# REP_-_Rev3.net
KiCad netlist of a schematic drawn in EAGLE
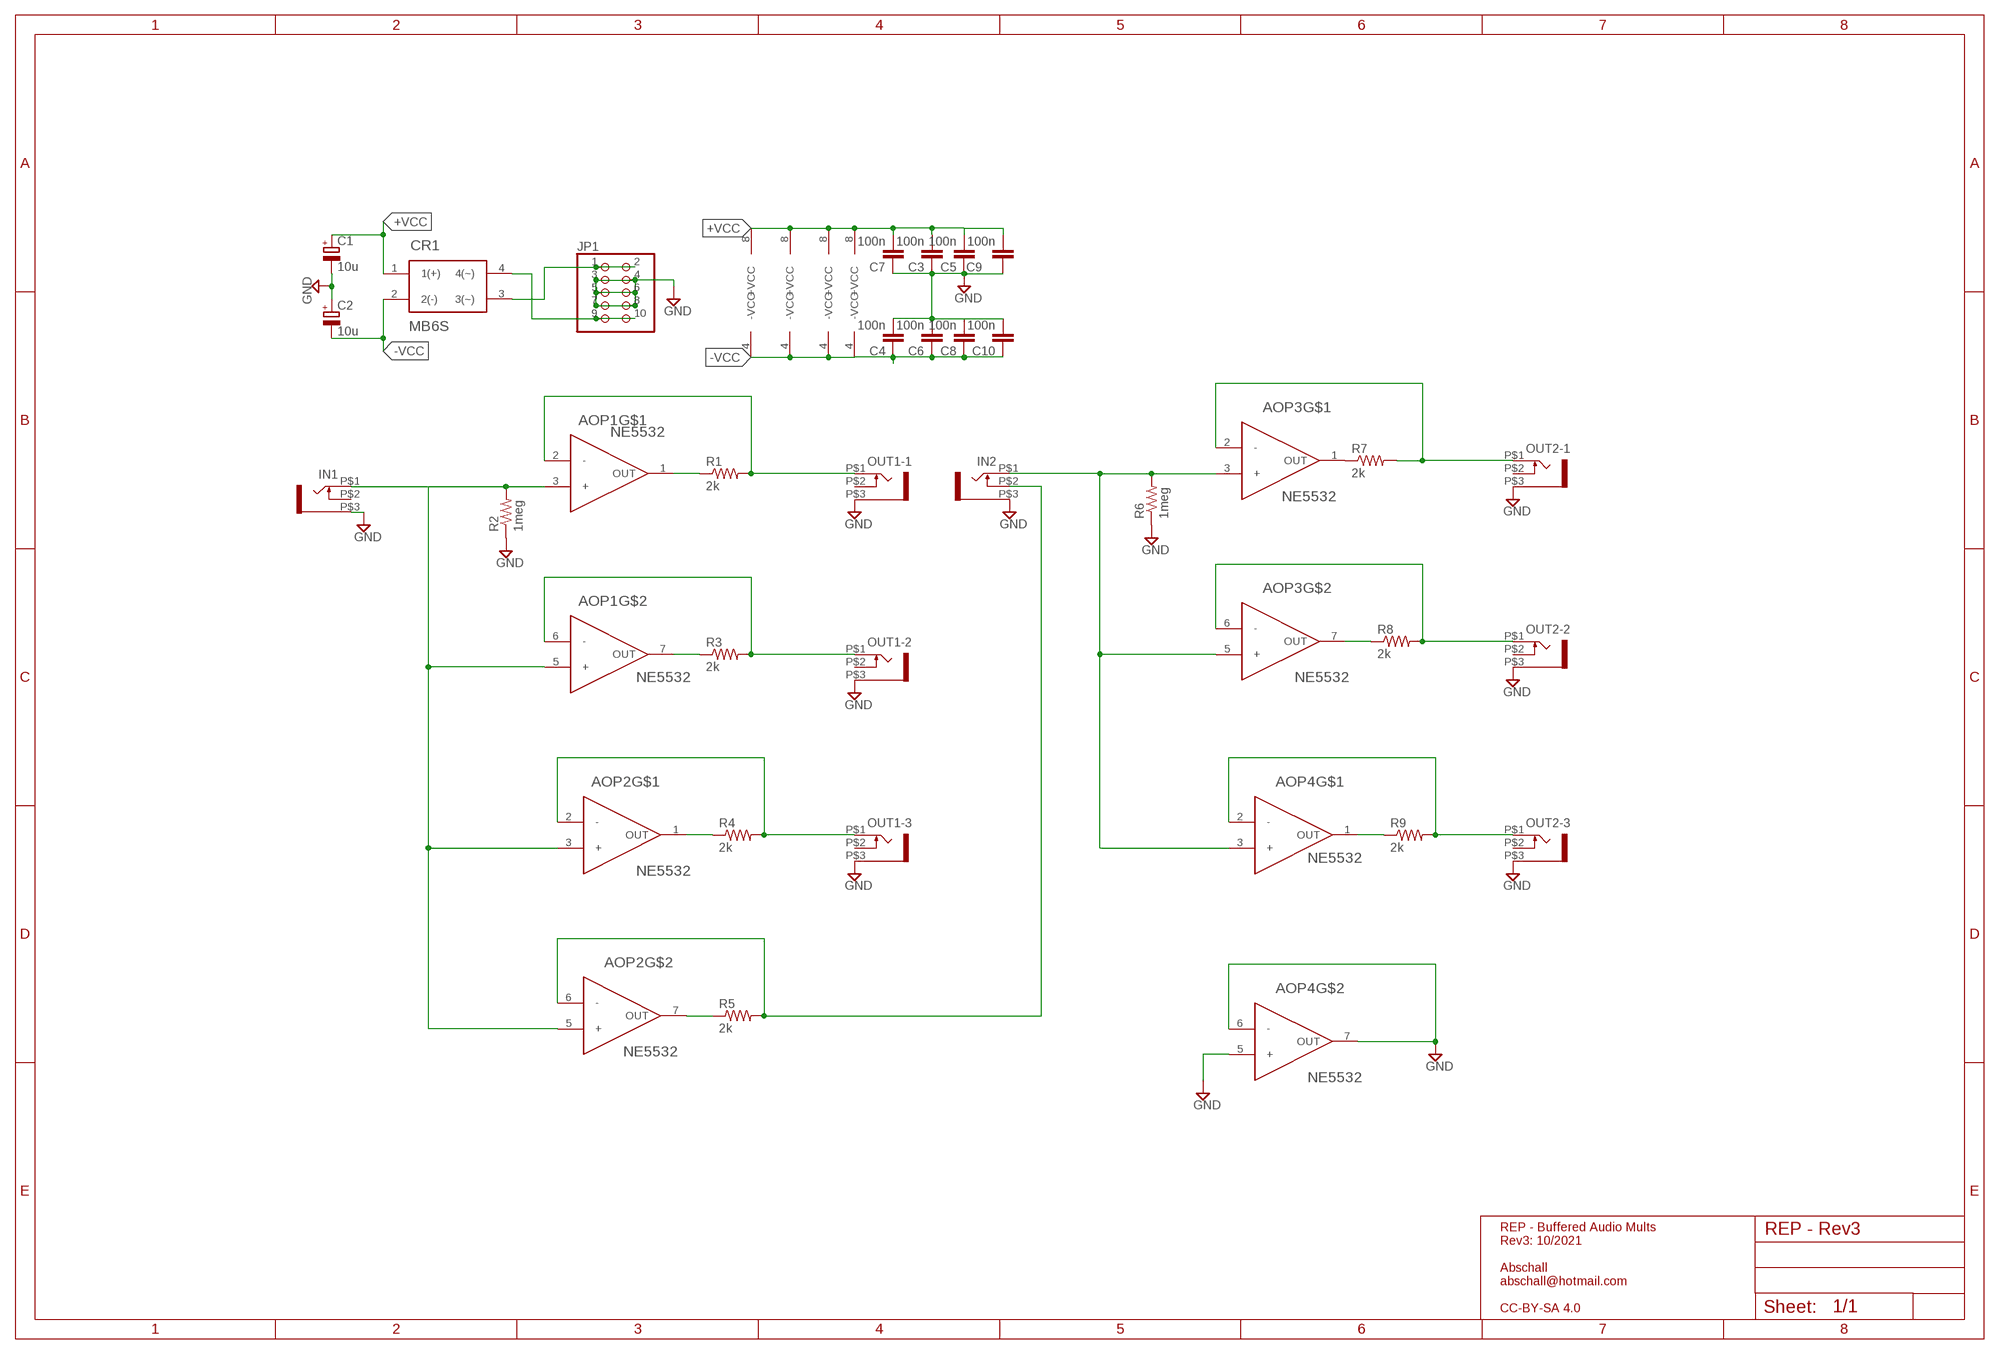
[diagram p0: schematic, sheet 1]

(export (version "E")
  (design (tool "Eeschema 10.0.6"))
  (components
    (comp (ref "AOP1")
      (value "NE5532")
      (footprint "eagle-import:SOIC8")
      (libsource (lib "eagle-import") (part "TL072ACDR"))
    )
    (comp (ref "AOP2")
      (value "NE5532")
      (footprint "eagle-import:SOIC8")
      (libsource (lib "eagle-import") (part "TL072ACDR"))
    )
    (comp (ref "AOP3")
      (value "NE5532")
      (footprint "eagle-import:SOIC8")
      (libsource (lib "eagle-import") (part "TL072ACDR"))
    )
    (comp (ref "AOP4")
      (value "NE5532")
      (footprint "eagle-import:SOIC8")
      (libsource (lib "eagle-import") (part "TL072ACDR"))
    )
    (comp (ref "C1")
      (value "10u")
      (footprint "eagle-import:PANASONIC_B")
      (libsource (lib "eagle-import") (part "CPOL-EUB"))
    )
    (comp (ref "C2")
      (value "10u")
      (footprint "eagle-import:PANASONIC_B")
      (libsource (lib "eagle-import") (part "CPOL-EUB"))
    )
    (comp (ref "C3")
      (value "100n")
      (footprint "eagle-import:C0805")
      (libsource (lib "eagle-import") (part "C-EUC0805"))
    )
    (comp (ref "C4")
      (value "100n")
      (footprint "eagle-import:C0805")
      (libsource (lib "eagle-import") (part "C-EUC0805"))
    )
    (comp (ref "C5")
      (value "100n")
      (footprint "eagle-import:C0805")
      (libsource (lib "eagle-import") (part "C-EUC0805"))
    )
    (comp (ref "C6")
      (value "100n")
      (footprint "eagle-import:C0805")
      (libsource (lib "eagle-import") (part "C-EUC0805"))
    )
    (comp (ref "C7")
      (value "100n")
      (footprint "eagle-import:C0805")
      (libsource (lib "eagle-import") (part "C-EUC0805"))
    )
    (comp (ref "C8")
      (value "100n")
      (footprint "eagle-import:C0805")
      (libsource (lib "eagle-import") (part "C-EUC0805"))
    )
    (comp (ref "C9")
      (value "100n")
      (footprint "eagle-import:C0805")
      (libsource (lib "eagle-import") (part "C-EUC0805"))
    )
    (comp (ref "C10")
      (value "100n")
      (footprint "eagle-import:C0805")
      (libsource (lib "eagle-import") (part "C-EUC0805"))
    )
    (comp (ref "CR1")
      (value "MB6S")
      (footprint "eagle-import:4SOIC")
      (fields
        (field (name "DIGIKEY_PARTNO") "MB6SCT-ND")
        (field (name "MANUFACTURER") "ON Semiconductor")
        (field (name "CREATED_BY") "PCBLayout.com")
      )
      (libsource (lib "eagle-import") (part "MB6S"))
    )
    (comp (ref "IN1")
      (value "WQP-PJ301M-12_JACK")
      (footprint "eagle-import:WQP-PJ301M-12_JACK")
      (libsource (lib "eagle-import") (part "WQP-PJ301M-12_JACK"))
    )
    (comp (ref "IN2")
      (value "WQP-PJ301M-12_JACK")
      (footprint "eagle-import:WQP-PJ301M-12_JACK")
      (libsource (lib "eagle-import") (part "WQP-PJ301M-12_JACK"))
    )
    (comp (ref "JP1")
      (value "PINHD-2X5")
      (footprint "eagle-import:2X05")
      (libsource (lib "eagle-import") (part "PINHD-2X5"))
    )
    (comp (ref "OUT1-1")
      (value "WQP-PJ301M-12_JACK")
      (footprint "eagle-import:WQP-PJ301M-12_JACK")
      (libsource (lib "eagle-import") (part "WQP-PJ301M-12_JACK"))
    )
    (comp (ref "OUT1-2")
      (value "WQP-PJ301M-12_JACK")
      (footprint "eagle-import:WQP-PJ301M-12_JACK")
      (libsource (lib "eagle-import") (part "WQP-PJ301M-12_JACK"))
    )
    (comp (ref "OUT1-3")
      (value "WQP-PJ301M-12_JACK")
      (footprint "eagle-import:WQP-PJ301M-12_JACK")
      (libsource (lib "eagle-import") (part "WQP-PJ301M-12_JACK"))
    )
    (comp (ref "OUT2-1")
      (value "WQP-PJ301M-12_JACK")
      (footprint "eagle-import:WQP-PJ301M-12_JACK")
      (libsource (lib "eagle-import") (part "WQP-PJ301M-12_JACK"))
    )
    (comp (ref "OUT2-2")
      (value "WQP-PJ301M-12_JACK")
      (footprint "eagle-import:WQP-PJ301M-12_JACK")
      (libsource (lib "eagle-import") (part "WQP-PJ301M-12_JACK"))
    )
    (comp (ref "OUT2-3")
      (value "WQP-PJ301M-12_JACK")
      (footprint "eagle-import:WQP-PJ301M-12_JACK")
      (libsource (lib "eagle-import") (part "WQP-PJ301M-12_JACK"))
    )
    (comp (ref "R1")
      (value "2k")
      (footprint "eagle-import:R0805")
      (libsource (lib "eagle-import") (part "R-US_R0805"))
    )
    (comp (ref "R2")
      (value "1meg")
      (footprint "eagle-import:R0805")
      (libsource (lib "eagle-import") (part "R-US_R0805"))
    )
    (comp (ref "R3")
      (value "2k")
      (footprint "eagle-import:R0805")
      (libsource (lib "eagle-import") (part "R-US_R0805"))
    )
    (comp (ref "R4")
      (value "2k")
      (footprint "eagle-import:R0805")
      (libsource (lib "eagle-import") (part "R-US_R0805"))
    )
    (comp (ref "R5")
      (value "2k")
      (footprint "eagle-import:R0805")
      (libsource (lib "eagle-import") (part "R-US_R0805"))
    )
    (comp (ref "R6")
      (value "1meg")
      (footprint "eagle-import:R0805")
      (libsource (lib "eagle-import") (part "R-US_R0805"))
    )
    (comp (ref "R7")
      (value "2k")
      (footprint "eagle-import:R0805")
      (libsource (lib "eagle-import") (part "R-US_R0805"))
    )
    (comp (ref "R8")
      (value "2k")
      (footprint "eagle-import:R0805")
      (libsource (lib "eagle-import") (part "R-US_R0805"))
    )
    (comp (ref "R9")
      (value "2k")
      (footprint "eagle-import:R0805")
      (libsource (lib "eagle-import") (part "R-US_R0805"))
    )
  )
  (nets
    (net (code "1") (name "+VCC") (class "Default")
      (node (ref "AOP1") (pin "8") (pinfunction "+VCC_8") (pintype "power_in"))
      (node (ref "AOP2") (pin "8") (pinfunction "+VCC_8") (pintype "power_in"))
      (node (ref "AOP3") (pin "8") (pinfunction "+VCC_8") (pintype "power_in"))
      (node (ref "AOP4") (pin "8") (pinfunction "+VCC_8") (pintype "power_in"))
      (node (ref "C1") (pin "+") (pinfunction "+_+") (pintype "passive"))
      (node (ref "C3") (pin "2") (pinfunction "2_2") (pintype "passive"))
      (node (ref "C5") (pin "2") (pinfunction "2_2") (pintype "passive"))
      (node (ref "C7") (pin "2") (pinfunction "2_2") (pintype "passive"))
      (node (ref "C9") (pin "2") (pinfunction "2_2") (pintype "passive"))
      (node (ref "CR1") (pin "1") (pinfunction "1(+)_1") (pintype "passive"))
    )
    (net (code "2") (name "-VCC") (class "Default")
      (node (ref "AOP1") (pin "4") (pinfunction "-VCC_4") (pintype "power_in"))
      (node (ref "AOP2") (pin "4") (pinfunction "-VCC_4") (pintype "power_in"))
      (node (ref "AOP3") (pin "4") (pinfunction "-VCC_4") (pintype "power_in"))
      (node (ref "AOP4") (pin "4") (pinfunction "-VCC_4") (pintype "power_in"))
      (node (ref "C10") (pin "1") (pinfunction "1_1") (pintype "passive"))
      (node (ref "C2") (pin "-") (pinfunction "-_-") (pintype "passive"))
      (node (ref "C4") (pin "1") (pinfunction "1_1") (pintype "passive"))
      (node (ref "C6") (pin "1") (pinfunction "1_1") (pintype "passive"))
      (node (ref "C8") (pin "1") (pinfunction "1_1") (pintype "passive"))
      (node (ref "CR1") (pin "2") (pinfunction "2(-)_2") (pintype "passive"))
    )
    (net (code "3") (name "GND") (class "Default")
      (node (ref "AOP4") (pin "5") (pinfunction "+_5") (pintype "input"))
      (node (ref "AOP4") (pin "6") (pinfunction "-_6") (pintype "input"))
      (node (ref "AOP4") (pin "7") (pinfunction "OUT_7") (pintype "output"))
      (node (ref "C1") (pin "-") (pinfunction "-_-") (pintype "passive"))
      (node (ref "C2") (pin "+") (pinfunction "+_+") (pintype "passive"))
      (node (ref "C3") (pin "1") (pinfunction "1_1") (pintype "passive"))
      (node (ref "C4") (pin "2") (pinfunction "2_2") (pintype "passive"))
      (node (ref "C5") (pin "1") (pinfunction "1_1") (pintype "passive"))
      (node (ref "C6") (pin "2") (pinfunction "2_2") (pintype "passive"))
      (node (ref "C7") (pin "1") (pinfunction "1_1") (pintype "passive"))
      (node (ref "C8") (pin "2") (pinfunction "2_2") (pintype "passive"))
      (node (ref "C9") (pin "1") (pinfunction "1_1") (pintype "passive"))
      (node (ref "IN1") (pin "P$3") (pinfunction "1_P$3") (pintype "passive"))
      (node (ref "IN2") (pin "P$3") (pinfunction "1_P$3") (pintype "passive"))
      (node (ref "JP1") (pin "3") (pinfunction "3_3") (pintype "passive"))
      (node (ref "JP1") (pin "4") (pinfunction "4_4") (pintype "passive"))
      (node (ref "JP1") (pin "5") (pinfunction "5_5") (pintype "passive"))
      (node (ref "JP1") (pin "6") (pinfunction "6_6") (pintype "passive"))
      (node (ref "JP1") (pin "7") (pinfunction "7_7") (pintype "passive"))
      (node (ref "JP1") (pin "8") (pinfunction "8_8") (pintype "passive"))
      (node (ref "OUT1-1") (pin "P$3") (pinfunction "1_P$3") (pintype "passive"))
      (node (ref "OUT1-2") (pin "P$3") (pinfunction "1_P$3") (pintype "passive"))
      (node (ref "OUT1-3") (pin "P$3") (pinfunction "1_P$3") (pintype "passive"))
      (node (ref "OUT2-1") (pin "P$3") (pinfunction "1_P$3") (pintype "passive"))
      (node (ref "OUT2-2") (pin "P$3") (pinfunction "1_P$3") (pintype "passive"))
      (node (ref "OUT2-3") (pin "P$3") (pinfunction "1_P$3") (pintype "passive"))
      (node (ref "R2") (pin "1") (pinfunction "1_1") (pintype "passive"))
      (node (ref "R6") (pin "1") (pinfunction "1_1") (pintype "passive"))
    )
    (net (code "4") (name "Net-(AOP1A-+)") (class "Default")
      (node (ref "AOP1") (pin "3") (pinfunction "+_3") (pintype "input"))
      (node (ref "AOP1") (pin "5") (pinfunction "+_5") (pintype "input"))
      (node (ref "AOP2") (pin "3") (pinfunction "+_3") (pintype "input"))
      (node (ref "AOP2") (pin "5") (pinfunction "+_5") (pintype "input"))
      (node (ref "IN1") (pin "P$1") (pinfunction "2_P$1") (pintype "passive"))
      (node (ref "R2") (pin "2") (pinfunction "2_2") (pintype "passive"))
    )
    (net (code "5") (name "Net-(AOP1A--)") (class "Default")
      (node (ref "AOP1") (pin "2") (pinfunction "-_2") (pintype "input"))
      (node (ref "OUT1-1") (pin "P$1") (pinfunction "2_P$1") (pintype "passive"))
      (node (ref "R1") (pin "2") (pinfunction "2_2") (pintype "passive"))
    )
    (net (code "6") (name "Net-(AOP1A-OUT)") (class "Default")
      (node (ref "AOP1") (pin "1") (pinfunction "OUT_1") (pintype "output"))
      (node (ref "R1") (pin "1") (pinfunction "1_1") (pintype "passive"))
    )
    (net (code "7") (name "Net-(AOP1B--)") (class "Default")
      (node (ref "AOP1") (pin "6") (pinfunction "-_6") (pintype "input"))
      (node (ref "OUT1-2") (pin "P$1") (pinfunction "2_P$1") (pintype "passive"))
      (node (ref "R3") (pin "2") (pinfunction "2_2") (pintype "passive"))
    )
    (net (code "8") (name "Net-(AOP1B-OUT)") (class "Default")
      (node (ref "AOP1") (pin "7") (pinfunction "OUT_7") (pintype "output"))
      (node (ref "R3") (pin "1") (pinfunction "1_1") (pintype "passive"))
    )
    (net (code "9") (name "Net-(AOP2A--)") (class "Default")
      (node (ref "AOP2") (pin "2") (pinfunction "-_2") (pintype "input"))
      (node (ref "OUT1-3") (pin "P$1") (pinfunction "2_P$1") (pintype "passive"))
      (node (ref "R4") (pin "2") (pinfunction "2_2") (pintype "passive"))
    )
    (net (code "10") (name "Net-(AOP2A-OUT)") (class "Default")
      (node (ref "AOP2") (pin "1") (pinfunction "OUT_1") (pintype "output"))
      (node (ref "R4") (pin "1") (pinfunction "1_1") (pintype "passive"))
    )
    (net (code "11") (name "Net-(AOP2B--)") (class "Default")
      (node (ref "AOP2") (pin "6") (pinfunction "-_6") (pintype "input"))
      (node (ref "IN2") (pin "P$2") (pinfunction "3_P$2") (pintype "passive"))
      (node (ref "R5") (pin "2") (pinfunction "2_2") (pintype "passive"))
    )
    (net (code "12") (name "Net-(AOP2B-OUT)") (class "Default")
      (node (ref "AOP2") (pin "7") (pinfunction "OUT_7") (pintype "output"))
      (node (ref "R5") (pin "1") (pinfunction "1_1") (pintype "passive"))
    )
    (net (code "13") (name "Net-(AOP3A-+)") (class "Default")
      (node (ref "AOP3") (pin "3") (pinfunction "+_3") (pintype "input"))
      (node (ref "AOP3") (pin "5") (pinfunction "+_5") (pintype "input"))
      (node (ref "AOP4") (pin "3") (pinfunction "+_3") (pintype "input"))
      (node (ref "IN2") (pin "P$1") (pinfunction "2_P$1") (pintype "passive"))
      (node (ref "R6") (pin "2") (pinfunction "2_2") (pintype "passive"))
    )
    (net (code "14") (name "Net-(AOP3A--)") (class "Default")
      (node (ref "AOP3") (pin "2") (pinfunction "-_2") (pintype "input"))
      (node (ref "OUT2-1") (pin "P$1") (pinfunction "2_P$1") (pintype "passive"))
      (node (ref "R7") (pin "2") (pinfunction "2_2") (pintype "passive"))
    )
    (net (code "15") (name "Net-(AOP3A-OUT)") (class "Default")
      (node (ref "AOP3") (pin "1") (pinfunction "OUT_1") (pintype "output"))
      (node (ref "R7") (pin "1") (pinfunction "1_1") (pintype "passive"))
    )
    (net (code "16") (name "Net-(AOP3B--)") (class "Default")
      (node (ref "AOP3") (pin "6") (pinfunction "-_6") (pintype "input"))
      (node (ref "OUT2-2") (pin "P$1") (pinfunction "2_P$1") (pintype "passive"))
      (node (ref "R8") (pin "2") (pinfunction "2_2") (pintype "passive"))
    )
    (net (code "17") (name "Net-(AOP3B-OUT)") (class "Default")
      (node (ref "AOP3") (pin "7") (pinfunction "OUT_7") (pintype "output"))
      (node (ref "R8") (pin "1") (pinfunction "1_1") (pintype "passive"))
    )
    (net (code "18") (name "Net-(AOP4A--)") (class "Default")
      (node (ref "AOP4") (pin "2") (pinfunction "-_2") (pintype "input"))
      (node (ref "OUT2-3") (pin "P$1") (pinfunction "2_P$1") (pintype "passive"))
      (node (ref "R9") (pin "2") (pinfunction "2_2") (pintype "passive"))
    )
    (net (code "19") (name "Net-(AOP4A-OUT)") (class "Default")
      (node (ref "AOP4") (pin "1") (pinfunction "OUT_1") (pintype "output"))
      (node (ref "R9") (pin "1") (pinfunction "1_1") (pintype "passive"))
    )
    (net (code "20") (name "Net-(CR1-3(~{}))") (class "Default")
      (node (ref "CR1") (pin "3") (pinfunction "3(~{})_3") (pintype "passive"))
      (node (ref "JP1") (pin "1") (pinfunction "1_1") (pintype "passive"))
      (node (ref "JP1") (pin "2") (pinfunction "2_2") (pintype "passive"))
    )
    (net (code "21") (name "Net-(CR1-4(~{}))") (class "Default")
      (node (ref "CR1") (pin "4") (pinfunction "4(~{})_4") (pintype "passive"))
      (node (ref "JP1") (pin "10") (pinfunction "10_10") (pintype "passive"))
      (node (ref "JP1") (pin "9") (pinfunction "9_9") (pintype "passive"))
    )
    (net (code "22") (name "unconnected-(C10-Pad2)") (class "Default")
      (node (ref "C10") (pin "2") (pinfunction "2_2") (pintype "passive"))
    )
    (net (code "23") (name "unconnected-(IN1-3-PadP$2)") (class "Default")
      (node (ref "IN1") (pin "P$2") (pinfunction "3_P$2") (pintype "passive"))
    )
    (net (code "24") (name "unconnected-(OUT1-1-3-PadP$2)") (class "Default")
      (node (ref "OUT1-1") (pin "P$2") (pinfunction "3_P$2") (pintype "passive"))
    )
    (net (code "25") (name "unconnected-(OUT1-2-3-PadP$2)") (class "Default")
      (node (ref "OUT1-2") (pin "P$2") (pinfunction "3_P$2") (pintype "passive"))
    )
    (net (code "26") (name "unconnected-(OUT1-3-3-PadP$2)") (class "Default")
      (node (ref "OUT1-3") (pin "P$2") (pinfunction "3_P$2") (pintype "passive"))
    )
    (net (code "27") (name "unconnected-(OUT2-1-3-PadP$2)") (class "Default")
      (node (ref "OUT2-1") (pin "P$2") (pinfunction "3_P$2") (pintype "passive"))
    )
    (net (code "28") (name "unconnected-(OUT2-2-3-PadP$2)") (class "Default")
      (node (ref "OUT2-2") (pin "P$2") (pinfunction "3_P$2") (pintype "passive"))
    )
    (net (code "29") (name "unconnected-(OUT2-3-3-PadP$2)") (class "Default")
      (node (ref "OUT2-3") (pin "P$2") (pinfunction "3_P$2") (pintype "passive"))
    )
  )
)
